# 1750_master_remote.net
KiCad netlist of a schematic drawn in EAGLE
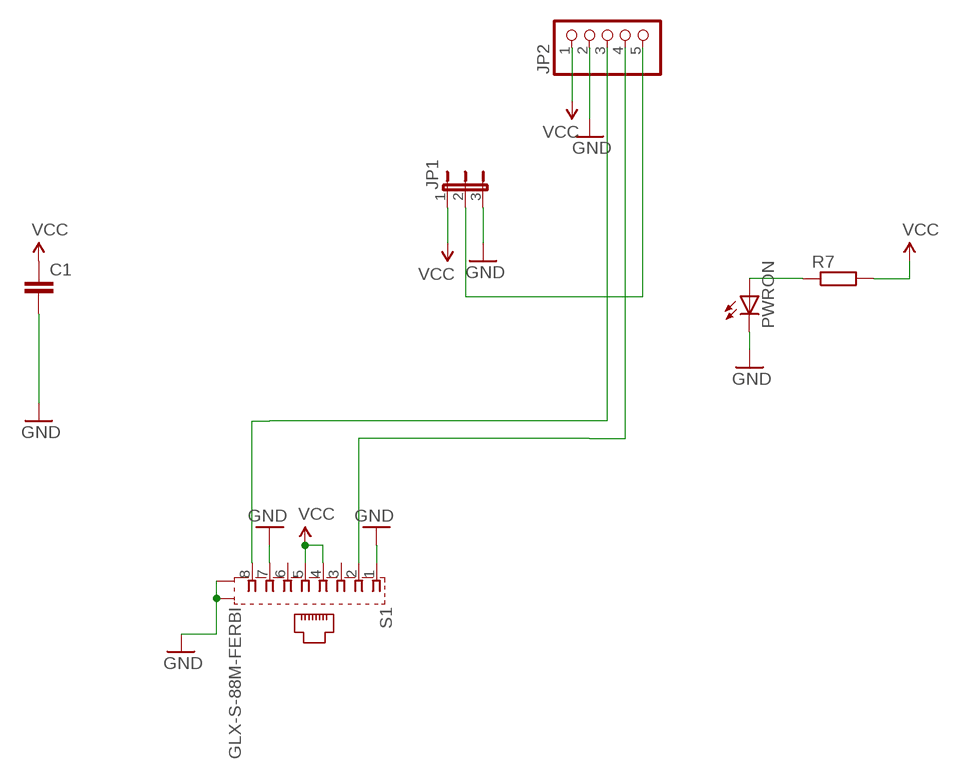
[diagram p0: schematic, sheet 1]

(export (version "E")
  (design (tool "Eeschema 10.0.6"))
  (components
    (comp (ref "C1")
      (value "C-EU025-025X050")
      (footprint "eagle-import:C025-025X050")
      (libsource (lib "eagle-import") (part "C-EU025-025X050"))
    )
    (comp (ref "JP1")
      (value "JP2E")
      (footprint "eagle-import:JP2")
      (libsource (lib "eagle-import") (part "JP2E"))
    )
    (comp (ref "JP2")
      (value "PINHD-1X5")
      (footprint "eagle-import:1X05")
      (libsource (lib "eagle-import") (part "PINHD-1X5"))
    )
    (comp (ref "PWRON")
      (value "LED5MM")
      (footprint "eagle-import:LED5MM")
      (libsource (lib "eagle-import") (part "LED5MM"))
    )
    (comp (ref "R7")
      (value "R-EU_0207/10")
      (footprint "eagle-import:0207_10")
      (libsource (lib "eagle-import") (part "R-EU_0207/10"))
    )
    (comp (ref "S1")
      (value "GLX-S-88M-FERBI")
      (footprint "eagle-import:GLX-S-88M-FERBI")
      (libsource (lib "eagle-import") (part "GLX-S-88M-FERBI"))
    )
  )
  (nets
    (net (code "1") (name "GND") (class "Default")
      (node (ref "C1") (pin "2") (pinfunction "2_2") (pintype "passive"))
      (node (ref "JP1") (pin "3") (pinfunction "3_3") (pintype "passive"))
      (node (ref "JP2") (pin "2") (pinfunction "2_2") (pintype "passive"))
      (node (ref "PWRON") (pin "K") (pinfunction "C_K") (pintype "passive"))
      (node (ref "S1") (pin "1") (pinfunction "1_1") (pintype "passive"))
      (node (ref "S1") (pin "7") (pinfunction "7_7") (pintype "passive"))
      (node (ref "S1") (pin "S1") (pinfunction "S1_S1") (pintype "passive"))
      (node (ref "S1") (pin "S2") (pinfunction "S2_S2") (pintype "passive"))
    )
    (net (code "2") (name "Net-(JP1-Pad2)") (class "Default")
      (node (ref "JP1") (pin "2") (pinfunction "2_2") (pintype "passive"))
      (node (ref "JP2") (pin "5") (pinfunction "5_5") (pintype "passive"))
    )
    (net (code "3") (name "Net-(JP2-Pad3)") (class "Default")
      (node (ref "JP2") (pin "3") (pinfunction "3_3") (pintype "passive"))
      (node (ref "S1") (pin "8") (pinfunction "8_8") (pintype "passive"))
    )
    (net (code "4") (name "Net-(JP2-Pad4)") (class "Default")
      (node (ref "JP2") (pin "4") (pinfunction "4_4") (pintype "passive"))
      (node (ref "S1") (pin "2") (pinfunction "2_2") (pintype "passive"))
    )
    (net (code "5") (name "Net-(PWRON-PadA)") (class "Default")
      (node (ref "PWRON") (pin "A") (pinfunction "A_A") (pintype "passive"))
      (node (ref "R7") (pin "1") (pinfunction "1_1") (pintype "passive"))
    )
    (net (code "6") (name "VCC") (class "Default")
      (node (ref "C1") (pin "1") (pinfunction "1_1") (pintype "passive"))
      (node (ref "JP1") (pin "1") (pinfunction "1_1") (pintype "passive"))
      (node (ref "JP2") (pin "1") (pinfunction "1_1") (pintype "passive"))
      (node (ref "R7") (pin "2") (pinfunction "2_2") (pintype "passive"))
      (node (ref "S1") (pin "4") (pinfunction "4_4") (pintype "passive"))
      (node (ref "S1") (pin "5") (pinfunction "5_5") (pintype "passive"))
    )
    (net (code "7") (name "unconnected-(S1-Pad3)") (class "Default")
      (node (ref "S1") (pin "3") (pinfunction "3_3") (pintype "passive"))
    )
    (net (code "8") (name "unconnected-(S1-Pad6)") (class "Default")
      (node (ref "S1") (pin "6") (pinfunction "6_6") (pintype "passive"))
    )
  )
)
